# 01-POWER.net
KiCad netlist of a schematic drawn in Altium Designer
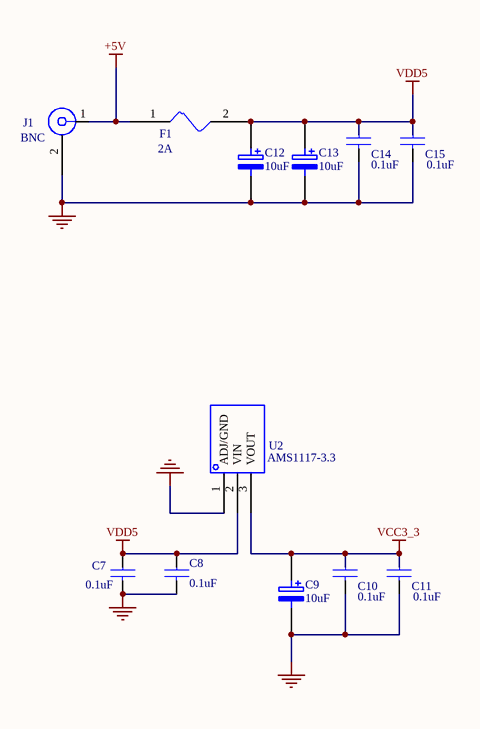
[diagram p0: 01-POWER.SchDoc]

(export (version "E")
  (design (tool "Eeschema 10.0.6"))
  (components
    (comp (ref "C7")
      (value "0.1uF")
      (footprint "0805-C")
      (fields (field (name "Comment") "10uF"))
      (libsource (lib "VIDEO_Demo_Kit_1") (part "CAP"))
    )
    (comp (ref "C8") (value "0.1uF") (footprint "C0603") (libsource (lib "VIDEO_Demo_Kit_1") (part "CAP")))
    (comp (ref "C9")
      (value "10uF")
      (footprint "3528-C")
      (description "Electrolytic Capacitor")
      (libsource (lib "*") (part "ELECTRO2"))
    )
    (comp (ref "C10") (value "0.1uF") (footprint "C0603") (libsource (lib "VIDEO_Demo_Kit_1") (part "CAP")))
    (comp (ref "C11") (value "0.1uF") (footprint "C0603") (libsource (lib "VIDEO_Demo_Kit_1") (part "CAP")))
    (comp (ref "C12")
      (value "10uF")
      (footprint "3528-C")
      (description "Electrolytic Capacitor")
      (libsource (lib "*") (part "ELECTRO2"))
    )
    (comp (ref "C13")
      (value "10uF")
      (footprint "3528-C")
      (description "Electrolytic Capacitor")
      (libsource (lib "*") (part "ELECTRO2"))
    )
    (comp (ref "C14") (value "0.1uF") (footprint "1206-C") (libsource (lib "VIDEO_Demo_Kit_1") (part "CAP")))
    (comp (ref "C15") (value "0.1uF") (footprint "1206-C") (libsource (lib "VIDEO_Demo_Kit_1") (part "CAP")))
    (comp (ref "F1")
      (value "2A")
      (footprint "1206-F")
      (fields (field (name "Comment") "FUSE"))
      (libsource (lib "VIDEO_Demo_Kit_1") (part "FUSE"))
    )
    (comp (ref "J1")
      (value "BNC")
      (footprint "DC-005B")
      (fields (field (name "SOURCE_PATH") "C:\\PROGRAM FILES\\印院出品\\CAPTURE 16.2\\LIBRARY\\CONNECTOR.OLB"))
      (libsource (lib "VIDEO_Demo_Kit_1") (part "BNC"))
    )
    (comp (ref "U2")
      (value "AMS1117-3.3")
      (footprint "SOT-89")
      (fields (field (name "Comment") "3.3_TO_1_0.8_VOLTAGE_REGULATOR"))
      (libsource (lib "VIDEO_Demo_Kit") (part "3.3_TO_1_0.8_VOLTAGE_REGULATOR"))
    )
  )
  (nets
    (net (code "1") (name "+5V") (class "Default")
      (node (ref "F1") (pin "1") (pinfunction "1_1") (pintype "passive"))
      (node (ref "J1") (pin "1") (pinfunction "CENTER_1") (pintype "passive"))
    )
    (net (code "2") (name "GND") (class "Default")
      (node (ref "C10") (pin "2") (pinfunction "2_2") (pintype "passive"))
      (node (ref "C11") (pin "2") (pinfunction "2_2") (pintype "passive"))
      (node (ref "C12") (pin "2") (pinfunction "2_2") (pintype "passive"))
      (node (ref "C13") (pin "2") (pinfunction "2_2") (pintype "passive"))
      (node (ref "C14") (pin "2") (pinfunction "2_2") (pintype "passive"))
      (node (ref "C15") (pin "2") (pinfunction "2_2") (pintype "passive"))
      (node (ref "C7") (pin "2") (pinfunction "2_2") (pintype "passive"))
      (node (ref "C8") (pin "2") (pinfunction "2_2") (pintype "passive"))
      (node (ref "C9") (pin "2") (pinfunction "2_2") (pintype "passive"))
      (node (ref "J1") (pin "2") (pinfunction "SHIELD_2") (pintype "passive"))
      (node (ref "U2") (pin "1") (pinfunction "ADJ/GND_1") (pintype "passive"))
    )
    (net (code "3") (name "VCC3_3") (class "Default")
      (node (ref "C10") (pin "1") (pinfunction "1_1") (pintype "passive"))
      (node (ref "C11") (pin "1") (pinfunction "1_1") (pintype "passive"))
      (node (ref "C9") (pin "1") (pinfunction "1_1") (pintype "passive"))
      (node (ref "U2") (pin "3") (pinfunction "VOUT_3") (pintype "passive"))
    )
    (net (code "4") (name "VDD5") (class "Default")
      (node (ref "C12") (pin "1") (pinfunction "1_1") (pintype "passive"))
      (node (ref "C13") (pin "1") (pinfunction "1_1") (pintype "passive"))
      (node (ref "C14") (pin "1") (pinfunction "1_1") (pintype "passive"))
      (node (ref "C15") (pin "1") (pinfunction "1_1") (pintype "passive"))
      (node (ref "C7") (pin "1") (pinfunction "1_1") (pintype "passive"))
      (node (ref "C8") (pin "1") (pinfunction "1_1") (pintype "passive"))
      (node (ref "F1") (pin "2") (pinfunction "2_2") (pintype "passive"))
      (node (ref "U2") (pin "2") (pinfunction "VIN_2") (pintype "passive"))
    )
  )
)
